# attiny84_3Transistor.net
KiCad netlist of a schematic drawn in EAGLE
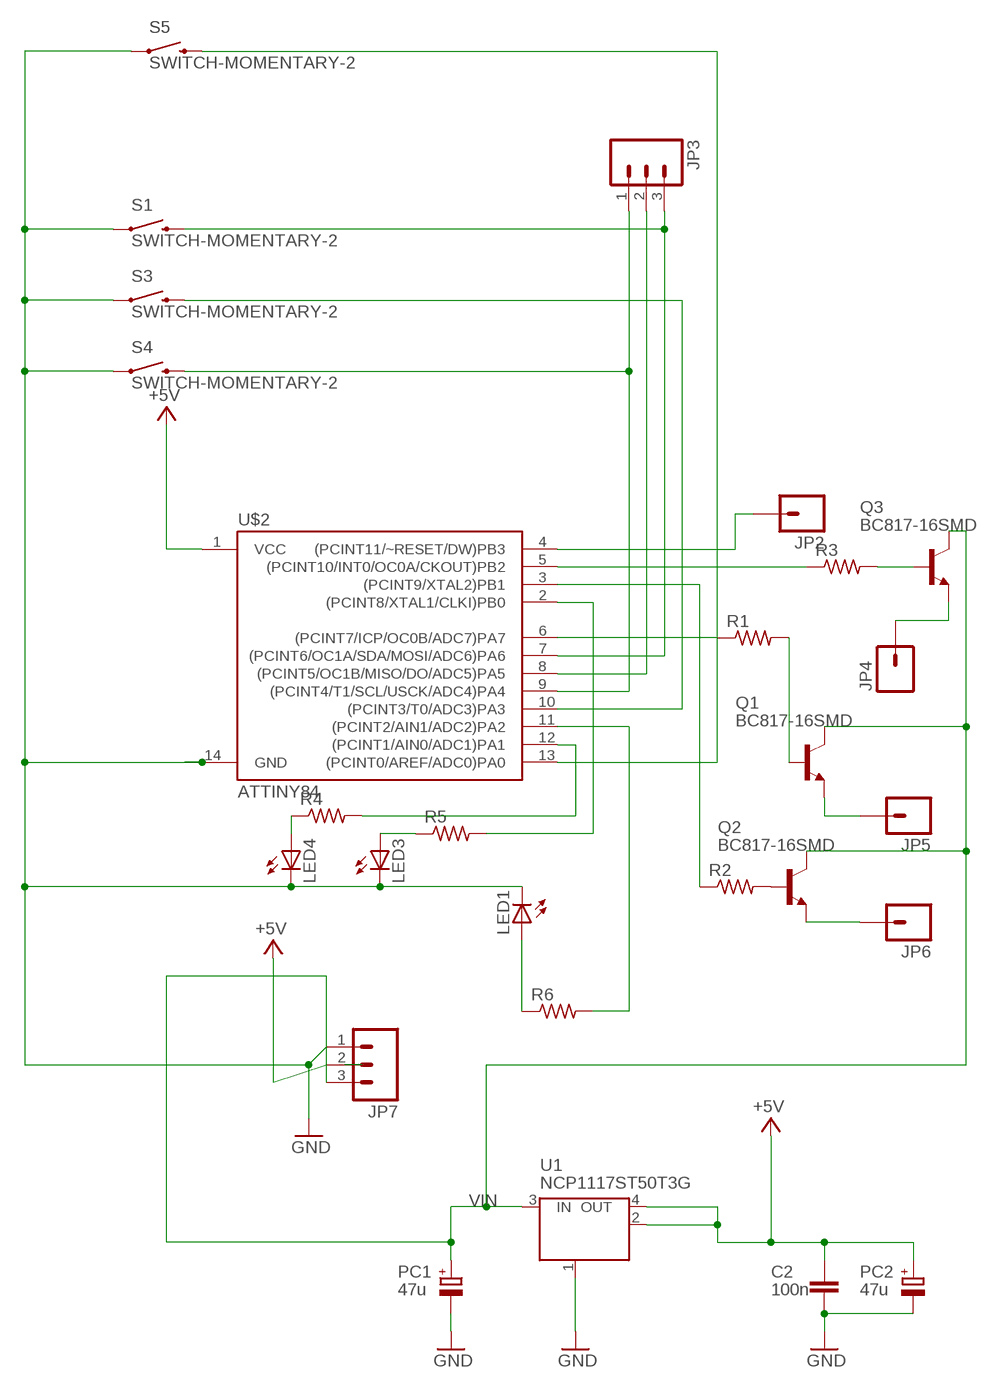
[diagram p0: schematic, sheet 1]

(export (version "E")
  (design (tool "Eeschema 10.0.6"))
  (components
    (comp (ref "C2")
      (value "100n")
      (footprint "eagle-import:C0603-ROUND")
      (libsource (lib "eagle-import") (part "C-EU0603-RND"))
    )
    (comp (ref "JP2")
      (value "M01NOSILK-KIT")
      (footprint "eagle-import:1X01NS-KIT")
      (libsource (lib "eagle-import") (part "M01NOSILK-KIT"))
    )
    (comp (ref "JP3")
      (value "M031X03_NO_SILK")
      (footprint "eagle-import:1X03_NO_SILK")
      (libsource (lib "eagle-import") (part "M031X03_NO_SILK"))
    )
    (comp (ref "JP4")
      (value "M01NOSILK-KIT")
      (footprint "eagle-import:1X01NS-KIT")
      (libsource (lib "eagle-import") (part "M01NOSILK-KIT"))
    )
    (comp (ref "JP5")
      (value "M01NOSILK-KIT")
      (footprint "eagle-import:1X01NS-KIT")
      (libsource (lib "eagle-import") (part "M01NOSILK-KIT"))
    )
    (comp (ref "JP6")
      (value "M01NOSILK-KIT")
      (footprint "eagle-import:1X01NS-KIT")
      (libsource (lib "eagle-import") (part "M01NOSILK-KIT"))
    )
    (comp (ref "JP7")
      (value "M031X03_NO_SILK")
      (footprint "eagle-import:1X03_NO_SILK")
      (libsource (lib "eagle-import") (part "M031X03_NO_SILK"))
    )
    (comp (ref "LED1")
      (value "LEDCHIPLED_0805")
      (footprint "eagle-import:CHIPLED_0805")
      (libsource (lib "eagle-import") (part "LEDCHIPLED_0805"))
    )
    (comp (ref "LED3")
      (value "LEDCHIPLED_0805")
      (footprint "eagle-import:CHIPLED_0805")
      (libsource (lib "eagle-import") (part "LEDCHIPLED_0805"))
    )
    (comp (ref "LED4")
      (value "LEDCHIPLED_0805")
      (footprint "eagle-import:CHIPLED_0805")
      (libsource (lib "eagle-import") (part "LEDCHIPLED_0805"))
    )
    (comp (ref "PC1")
      (value "47u")
      (footprint "eagle-import:E2,5-4R")
      (libsource (lib "eagle-import") (part "CPOL-EUE2.5-5V"))
    )
    (comp (ref "PC2")
      (value "47u")
      (footprint "eagle-import:E2,5-4R")
      (libsource (lib "eagle-import") (part "CPOL-EUE2.5-5V"))
    )
    (comp (ref "Q1")
      (value "BC817-16SMD")
      (footprint "eagle-import:SOT23-BEC")
      (libsource (lib "eagle-import") (part "BC817SMD-16"))
    )
    (comp (ref "Q2")
      (value "BC817-16SMD")
      (footprint "eagle-import:SOT23-BEC")
      (libsource (lib "eagle-import") (part "BC817SMD-16"))
    )
    (comp (ref "Q3")
      (value "BC817-16SMD")
      (footprint "eagle-import:SOT23-BEC")
      (libsource (lib "eagle-import") (part "BC817SMD-16"))
    )
    (comp (ref "R1")
      (value "R-US_M0805")
      (footprint "eagle-import:M0805")
      (libsource (lib "eagle-import") (part "R-US_M0805"))
    )
    (comp (ref "R2")
      (value "R-US_M0805")
      (footprint "eagle-import:M0805")
      (libsource (lib "eagle-import") (part "R-US_M0805"))
    )
    (comp (ref "R3")
      (value "R-US_M0805")
      (footprint "eagle-import:M0805")
      (libsource (lib "eagle-import") (part "R-US_M0805"))
    )
    (comp (ref "R4")
      (value "R-US_M0805")
      (footprint "eagle-import:M0805")
      (libsource (lib "eagle-import") (part "R-US_M0805"))
    )
    (comp (ref "R5")
      (value "R-US_M0805")
      (footprint "eagle-import:M0805")
      (libsource (lib "eagle-import") (part "R-US_M0805"))
    )
    (comp (ref "R6")
      (value "R-US_M0805")
      (footprint "eagle-import:M0805")
      (libsource (lib "eagle-import") (part "R-US_M0805"))
    )
    (comp (ref "S1")
      (value "SWITCH-MOMENTARY-2")
      (footprint "eagle-import:TACTILE_FSM4JSMATR")
      (libsource (lib "eagle-import") (part "SWITCH-MOMENTARY-2"))
    )
    (comp (ref "S3")
      (value "SWITCH-MOMENTARY-2")
      (footprint "eagle-import:TACTILE_FSM4JSMATR")
      (libsource (lib "eagle-import") (part "SWITCH-MOMENTARY-2"))
    )
    (comp (ref "S4")
      (value "SWITCH-MOMENTARY-2")
      (footprint "eagle-import:TACTILE_FSM4JSMATR")
      (libsource (lib "eagle-import") (part "SWITCH-MOMENTARY-2"))
    )
    (comp (ref "S5")
      (value "SWITCH-MOMENTARY-2")
      (footprint "eagle-import:TACTILE_FSM4JSMATR")
      (libsource (lib "eagle-import") (part "SWITCH-MOMENTARY-2"))
    )
    (comp (ref "U$2")
      (value "ATTINY84")
      (footprint "eagle-import:SO14")
      (libsource (lib "eagle-import") (part "ATTINY84"))
    )
    (comp (ref "U1")
      (value "NCP1117ST50T3G")
      (footprint "eagle-import:SOT223")
      (libsource (lib "eagle-import") (part "MC33269ST-3.3T3"))
    )
  )
  (nets
    (net (code "1") (name "+5V") (class "Default")
      (node (ref "C2") (pin "2") (pinfunction "2_2") (pintype "passive"))
      (node (ref "JP7") (pin "2") (pinfunction "2_2") (pintype "passive"))
      (node (ref "PC2") (pin "+") (pinfunction "+_+") (pintype "passive"))
      (node (ref "U$2") (pin "1") (pinfunction "VCC_1") (pintype "bidirectional"))
      (node (ref "U1") (pin "2") (pinfunction "OUT_2") (pintype "passive"))
      (node (ref "U1") (pin "4") (pinfunction "OUT_4") (pintype "passive"))
    )
    (net (code "2") (name "/VIN") (class "Default")
      (node (ref "JP7") (pin "3") (pinfunction "3_3") (pintype "passive"))
      (node (ref "PC1") (pin "+") (pinfunction "+_+") (pintype "passive"))
      (node (ref "Q1") (pin "C") (pinfunction "C_C") (pintype "passive"))
      (node (ref "Q2") (pin "C") (pinfunction "C_C") (pintype "passive"))
      (node (ref "Q3") (pin "C") (pinfunction "C_C") (pintype "passive"))
      (node (ref "U1") (pin "3") (pinfunction "IN_3") (pintype "input"))
    )
    (net (code "3") (name "GND") (class "Default")
      (node (ref "C2") (pin "1") (pinfunction "1_1") (pintype "passive"))
      (node (ref "JP7") (pin "1") (pinfunction "1_1") (pintype "passive"))
      (node (ref "LED1") (pin "C") (pinfunction "C_C") (pintype "passive"))
      (node (ref "LED3") (pin "C") (pinfunction "C_C") (pintype "passive"))
      (node (ref "LED4") (pin "C") (pinfunction "C_C") (pintype "passive"))
      (node (ref "PC1") (pin "-") (pinfunction "-_-") (pintype "passive"))
      (node (ref "PC2") (pin "-") (pinfunction "-_-") (pintype "passive"))
      (node (ref "S1") (pin "P$1") (pinfunction "1_P$1") (pintype "passive"))
      (node (ref "S1") (pin "P$2") (pinfunction "1_P$2") (pintype "passive"))
      (node (ref "S3") (pin "P$1") (pinfunction "1_P$1") (pintype "passive"))
      (node (ref "S3") (pin "P$2") (pinfunction "1_P$2") (pintype "passive"))
      (node (ref "S4") (pin "P$1") (pinfunction "1_P$1") (pintype "passive"))
      (node (ref "S4") (pin "P$2") (pinfunction "1_P$2") (pintype "passive"))
      (node (ref "S5") (pin "P$1") (pinfunction "1_P$1") (pintype "passive"))
      (node (ref "S5") (pin "P$2") (pinfunction "1_P$2") (pintype "passive"))
      (node (ref "U$2") (pin "14") (pinfunction "GND_14") (pintype "bidirectional"))
      (node (ref "U1") (pin "1") (pinfunction "GND/ADJ_1") (pintype "input"))
    )
    (net (code "4") (name "Net-(JP4-Pad1)") (class "Default")
      (node (ref "JP4") (pin "1") (pinfunction "1_1") (pintype "passive"))
      (node (ref "Q3") (pin "E") (pinfunction "E_E") (pintype "passive"))
    )
    (net (code "5") (name "Net-(JP5-Pad1)") (class "Default")
      (node (ref "JP5") (pin "1") (pinfunction "1_1") (pintype "passive"))
      (node (ref "Q1") (pin "E") (pinfunction "E_E") (pintype "passive"))
    )
    (net (code "6") (name "Net-(JP6-Pad1)") (class "Default")
      (node (ref "JP6") (pin "1") (pinfunction "1_1") (pintype "passive"))
      (node (ref "Q2") (pin "E") (pinfunction "E_E") (pintype "passive"))
    )
    (net (code "7") (name "Net-(LED1-PadA)") (class "Default")
      (node (ref "LED1") (pin "A") (pinfunction "A_A") (pintype "passive"))
      (node (ref "R6") (pin "1") (pinfunction "1_1") (pintype "passive"))
    )
    (net (code "8") (name "Net-(LED3-PadA)") (class "Default")
      (node (ref "LED3") (pin "A") (pinfunction "A_A") (pintype "passive"))
      (node (ref "R5") (pin "1") (pinfunction "1_1") (pintype "passive"))
    )
    (net (code "9") (name "Net-(LED4-PadA)") (class "Default")
      (node (ref "LED4") (pin "A") (pinfunction "A_A") (pintype "passive"))
      (node (ref "R4") (pin "1") (pinfunction "1_1") (pintype "passive"))
    )
    (net (code "10") (name "Net-(Q1-PadB)") (class "Default")
      (node (ref "Q1") (pin "B") (pinfunction "B_B") (pintype "passive"))
      (node (ref "R1") (pin "2") (pinfunction "2_2") (pintype "passive"))
    )
    (net (code "11") (name "Net-(Q2-PadB)") (class "Default")
      (node (ref "Q2") (pin "B") (pinfunction "B_B") (pintype "passive"))
      (node (ref "R2") (pin "2") (pinfunction "2_2") (pintype "passive"))
    )
    (net (code "12") (name "Net-(Q3-PadB)") (class "Default")
      (node (ref "Q3") (pin "B") (pinfunction "B_B") (pintype "passive"))
      (node (ref "R3") (pin "2") (pinfunction "2_2") (pintype "passive"))
    )
    (net (code "13") (name "Net-(U$2-(PCINT0{slash}AREF{slash}ADC0)PA0)") (class "Default")
      (node (ref "S5") (pin "P$3") (pinfunction "2_P$3") (pintype "passive"))
      (node (ref "S5") (pin "P$4") (pinfunction "2_P$4") (pintype "passive"))
      (node (ref "U$2") (pin "13") (pinfunction "(PCINT0/AREF/ADC0)PA0_13") (pintype "bidirectional"))
    )
    (net (code "14") (name "Net-(U$2-(PCINT1{slash}AIN0{slash}ADC1)PA1)") (class "Default")
      (node (ref "R4") (pin "2") (pinfunction "2_2") (pintype "passive"))
      (node (ref "U$2") (pin "12") (pinfunction "(PCINT1/AIN0/ADC1)PA1_12") (pintype "bidirectional"))
    )
    (net (code "15") (name "Net-(U$2-(PCINT2{slash}AIN1{slash}ADC2)PA2)") (class "Default")
      (node (ref "R6") (pin "2") (pinfunction "2_2") (pintype "passive"))
      (node (ref "U$2") (pin "11") (pinfunction "(PCINT2/AIN1/ADC2)PA2_11") (pintype "bidirectional"))
    )
    (net (code "16") (name "Net-(U$2-(PCINT3{slash}T0{slash}ADC3)PA3)") (class "Default")
      (node (ref "S3") (pin "P$3") (pinfunction "2_P$3") (pintype "passive"))
      (node (ref "S3") (pin "P$4") (pinfunction "2_P$4") (pintype "passive"))
      (node (ref "U$2") (pin "10") (pinfunction "(PCINT3/T0/ADC3)PA3_10") (pintype "bidirectional"))
    )
    (net (code "17") (name "Net-(U$2-(PCINT4{slash}T1{slash}SCL{slash}USCK{slash}ADC4)PA4)") (class "Default")
      (node (ref "JP3") (pin "1") (pinfunction "1_1") (pintype "passive"))
      (node (ref "S4") (pin "P$3") (pinfunction "2_P$3") (pintype "passive"))
      (node (ref "S4") (pin "P$4") (pinfunction "2_P$4") (pintype "passive"))
      (node (ref "U$2") (pin "9") (pinfunction "(PCINT4/T1/SCL/USCK/ADC4)PA4_9") (pintype "bidirectional"))
    )
    (net (code "18") (name "Net-(U$2-(PCINT5{slash}OC1B{slash}MISO{slash}DO{slash}ADC5)PA5)") (class "Default")
      (node (ref "JP3") (pin "2") (pinfunction "2_2") (pintype "passive"))
      (node (ref "U$2") (pin "8") (pinfunction "(PCINT5/OC1B/MISO/DO/ADC5)PA5_8") (pintype "bidirectional"))
    )
    (net (code "19") (name "Net-(U$2-(PCINT6{slash}OC1A{slash}SDA{slash}MOSI{slash}ADC6)PA6)") (class "Default")
      (node (ref "JP3") (pin "3") (pinfunction "3_3") (pintype "passive"))
      (node (ref "S1") (pin "P$3") (pinfunction "2_P$3") (pintype "passive"))
      (node (ref "S1") (pin "P$4") (pinfunction "2_P$4") (pintype "passive"))
      (node (ref "U$2") (pin "7") (pinfunction "(PCINT6/OC1A/SDA/MOSI/ADC6)PA6_7") (pintype "bidirectional"))
    )
    (net (code "20") (name "Net-(U$2-(PCINT7{slash}ICP{slash}OC0B{slash}ADC7)PA7)") (class "Default")
      (node (ref "R1") (pin "1") (pinfunction "1_1") (pintype "passive"))
      (node (ref "U$2") (pin "6") (pinfunction "(PCINT7/ICP/OC0B/ADC7)PA7_6") (pintype "bidirectional"))
    )
    (net (code "21") (name "Net-(U$2-(PCINT8{slash}XTAL1{slash}CLKI)PB0)") (class "Default")
      (node (ref "R5") (pin "2") (pinfunction "2_2") (pintype "passive"))
      (node (ref "U$2") (pin "2") (pinfunction "(PCINT8/XTAL1/CLKI)PB0_2") (pintype "bidirectional"))
    )
    (net (code "22") (name "Net-(U$2-(PCINT9{slash}XTAL2)PB1)") (class "Default")
      (node (ref "R2") (pin "1") (pinfunction "1_1") (pintype "passive"))
      (node (ref "U$2") (pin "3") (pinfunction "(PCINT9/XTAL2)PB1_3") (pintype "bidirectional"))
    )
    (net (code "23") (name "Net-(U$2-(PCINT10{slash}INT0{slash}OC0A{slash}CKOUT)PB2)") (class "Default")
      (node (ref "R3") (pin "1") (pinfunction "1_1") (pintype "passive"))
      (node (ref "U$2") (pin "5") (pinfunction "(PCINT10/INT0/OC0A/CKOUT)PB2_5") (pintype "bidirectional"))
    )
    (net (code "24") (name "Net-(U$2-(PCINT11{slash}~{RESET{slash}DW})PB3)") (class "Default")
      (node (ref "JP2") (pin "1") (pinfunction "1_1") (pintype "passive"))
      (node (ref "U$2") (pin "4") (pinfunction "(PCINT11/~{RESET/DW})PB3_4") (pintype "bidirectional"))
    )
  )
)
